# SCH_ESP32-v3_01-12-2025_2025-12-03.net
KiCad netlist of a schematic drawn in EasyEDA
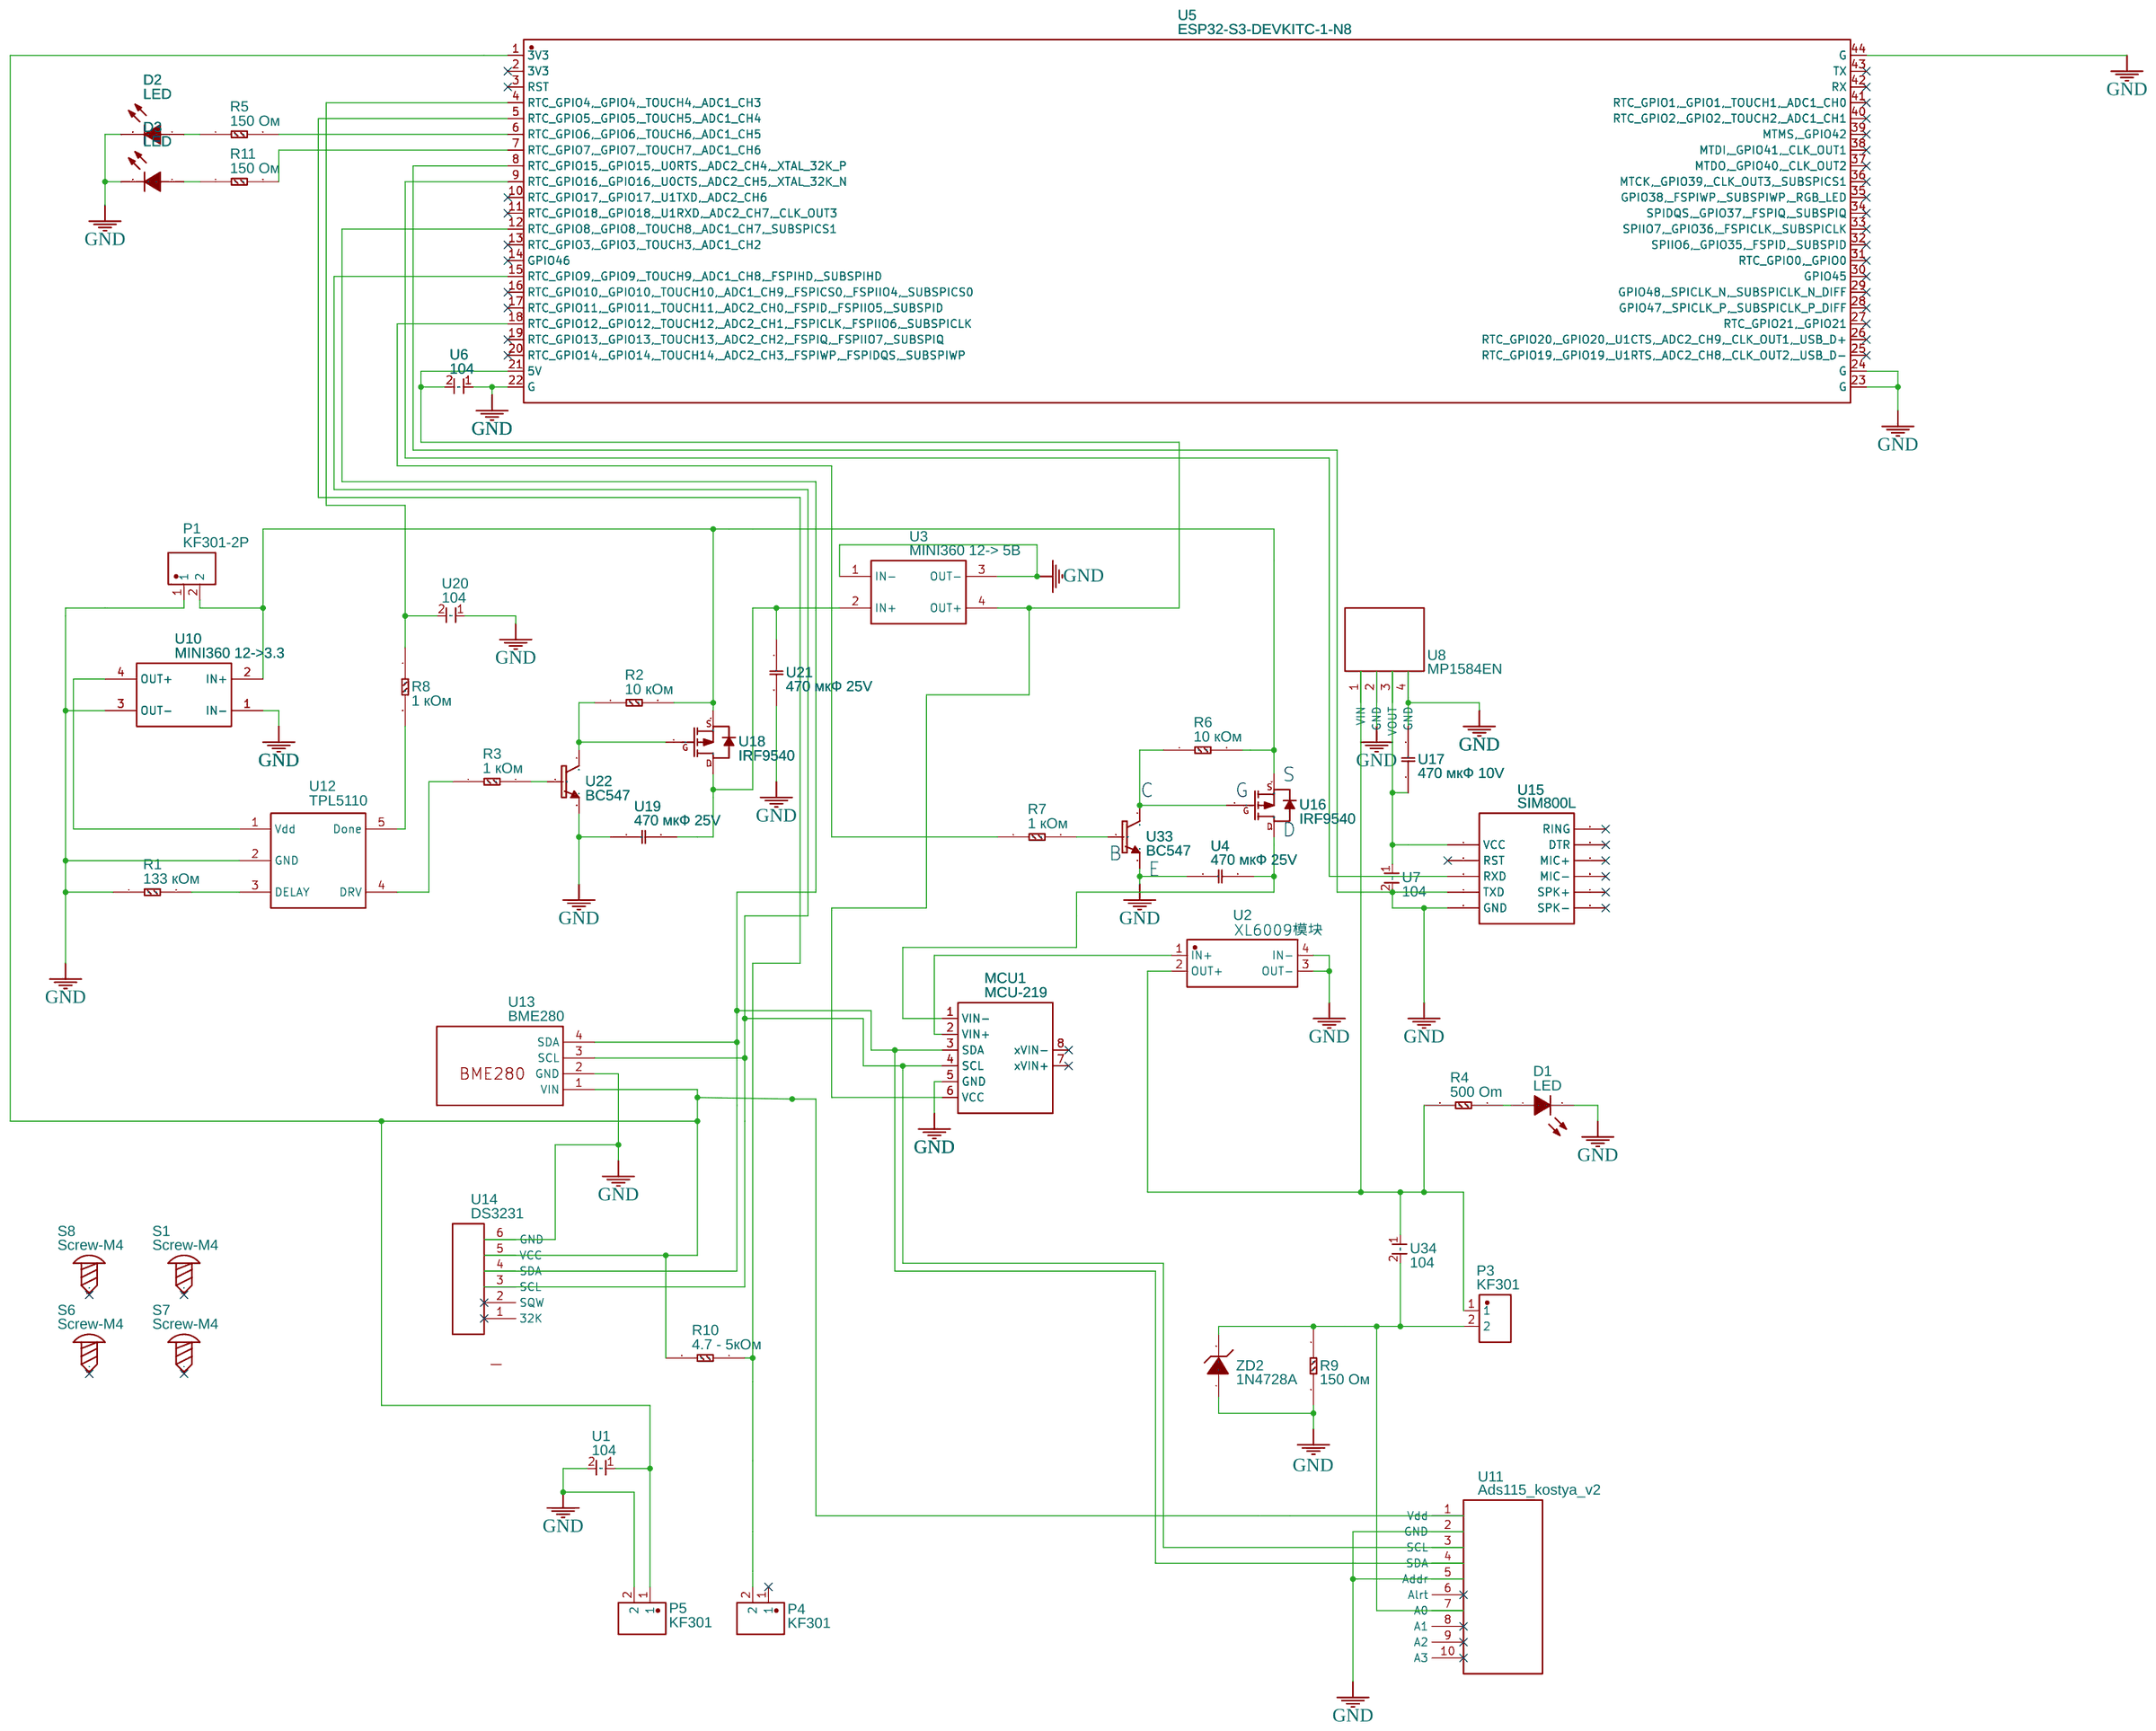
[diagram p0: schematic sheet]

(export (version "E")
  (design (tool "Eeschema 10.0.6"))
  (components
    (comp (ref "D1")
      (value "LED")
      (fields (field (name "Manufacturer Part") "5600") (field (name "Manufacturer") "VccLite"))
      (libsource (lib "") (part "LED_1"))
    )
    (comp (ref "D2")
      (value "LED")
      (fields (field (name "Manufacturer Part") "5600") (field (name "Manufacturer") "VccLite"))
      (libsource (lib "") (part "LED"))
    )
    (comp (ref "D3")
      (value "LED")
      (fields (field (name "Manufacturer Part") "5600") (field (name "Manufacturer") "VccLite"))
      (libsource (lib "") (part "LED"))
    )
    (comp (ref "MCU1") (value "MCU-219") (libsource (lib "") (part "MCU-219")))
    (comp (ref "P1")
      (value "KF301-2P")
      (fields (field (name "Manufacturer Part") "KF301-2P接线端子"))
      (libsource (lib "") (part "KF301-2P VCC Y GND"))
    )
    (comp (ref "P3")
      (value "KF301")
      (fields (field (name "Manufacturer Part") "KF301-2P接线端子"))
      (libsource (lib "") (part "KF301-2P VCC Y GND_2"))
    )
    (comp (ref "P4")
      (value "KF301")
      (fields (field (name "Manufacturer Part") "KF301-2P接线端子"))
      (libsource (lib "") (part "KF301-2P VCC Y GND_1"))
    )
    (comp (ref "P5")
      (value "KF301")
      (fields (field (name "Manufacturer Part") "KF301-2P接线端子"))
      (libsource (lib "") (part "KF301-2P VCC Y GND_1"))
    )
    (comp (ref "R1") (value "133 кОм") (libsource (lib "") (part "R_")))
    (comp (ref "R2") (value "10 кОм") (libsource (lib "") (part "R_")))
    (comp (ref "R3") (value "1 кОм") (libsource (lib "") (part "R_")))
    (comp (ref "R4") (value "500 Om") (libsource (lib "") (part "R__2")))
    (comp (ref "R5") (value "150 Ом") (libsource (lib "") (part "R_")))
    (comp (ref "R6") (value "10 кОм") (libsource (lib "") (part "R_")))
    (comp (ref "R7") (value "1 кОм") (libsource (lib "") (part "R_")))
    (comp (ref "R8") (value "1 кОм") (libsource (lib "") (part "R__1")))
    (comp (ref "R9") (value "150 Ом") (libsource (lib "") (part "R__1")))
    (comp (ref "R10") (value "4.7 - 5кОм") (libsource (lib "") (part "R__2")))
    (comp (ref "R11") (value "150 Ом") (libsource (lib "") (part "R_")))
    (comp (ref "S1") (value "Screw-M4") (libsource (lib "") (part "Screw-M4")))
    (comp (ref "S6") (value "Screw-M4") (libsource (lib "") (part "Screw-M4")))
    (comp (ref "S7") (value "Screw-M4") (libsource (lib "") (part "Screw-M4")))
    (comp (ref "S8") (value "Screw-M4") (libsource (lib "") (part "Screw-M4")))
    (comp (ref "U1")
      (value "104")
      (fields (field (name "Manufacturer") "Fe"))
      (libsource (lib "") (part "104_1"))
    )
    (comp (ref "U2")
      (value "XL6009模块")
      (fields (field (name "Manufacturer Part") "xl6009模块"))
      (libsource (lib "") (part "XL6009模块"))
    )
    (comp (ref "U3")
      (value "MINI360 12-> 5В")
      (fields (field (name "Manufacturer Part") "Mini360"))
      (libsource (lib "") (part "MINI360BUCK_1"))
    )
    (comp (ref "U4") (value "470 мкФ 25V") (libsource (lib "") (part "C__1")))
    (comp (ref "U5")
      (value "ESP32-S3-DEVKITC-1-N8")
      (fields (field (name "Manufacturer") "ESPRESSIF(乐鑫)"))
      (libsource (lib "") (part "ESP32-S3-DEVKITC-1-N8"))
    )
    (comp (ref "U6")
      (value "104")
      (fields (field (name "Manufacturer") "Fe"))
      (libsource (lib "") (part "104_1"))
    )
    (comp (ref "U7")
      (value "104")
      (fields (field (name "Manufacturer") "Fe"))
      (libsource (lib "") (part "104"))
    )
    (comp (ref "U8") (value "MP1584EN") (libsource (lib "") (part "MP1584EN")))
    (comp (ref "U10")
      (value "MINI360 12->3.3")
      (fields (field (name "Manufacturer Part") "Mini360"))
      (libsource (lib "") (part "MINI360BUCK"))
    )
    (comp (ref "U11") (value "Ads115_kostya_v2") (libsource (lib "") (part "Ads115_kostya_v2")))
    (comp (ref "U12")
      (value "TPL5110")
      (fields (field (name "Manufacturer Part") "3435"))
      (libsource (lib "") (part "ADAFRUIT TPL5110 BREAKOUT"))
    )
    (comp (ref "U13") (value "BME280") (libsource (lib "") (part "BME280")))
    (comp (ref "U14") (value "DS3231") (libsource (lib "") (part "DS3231 upright")))
    (comp (ref "U15") (value "SIM800L") (libsource (lib "") (part "SIM800L")))
    (comp (ref "U16") (value "IRF9540") (libsource (lib "") (part "IRF9540")))
    (comp (ref "U17") (value "470 мкФ 10V") (libsource (lib "") (part "C_")))
    (comp (ref "U18") (value "IRF9540") (libsource (lib "") (part "IRF9540")))
    (comp (ref "U19") (value "470 мкФ 25V") (libsource (lib "") (part "C__1")))
    (comp (ref "U20")
      (value "104")
      (fields (field (name "Manufacturer") "Fe"))
      (libsource (lib "") (part "104_1"))
    )
    (comp (ref "U21") (value "470 мкФ 25V") (libsource (lib "") (part "C_")))
    (comp (ref "U22") (value "BC547") (libsource (lib "") (part "BC547")))
    (comp (ref "U33") (value "BC547") (libsource (lib "") (part "BC547")))
    (comp (ref "U34")
      (value "104")
      (fields (field (name "Manufacturer") "Fe"))
      (libsource (lib "") (part "104"))
    )
    (comp (ref "ZD2")
      (value "1N4728A")
      (fields (field (name "Manufacturer") "ST(先科)"))
      (libsource (lib "") (part "1N4728A"))
    )
  )
  (nets
    (net (code "1") (name "GND") (class "Default")
      (node (ref "D1") (pin "2") (pinfunction "K_2") (pintype "unspecified"))
      (node (ref "D2") (pin "2") (pinfunction "K_2") (pintype "unspecified"))
      (node (ref "D3") (pin "2") (pinfunction "K_2") (pintype "unspecified"))
      (node (ref "MCU1") (pin "5") (pinfunction "GND_5") (pintype "unspecified"))
      (node (ref "P1") (pin "1") (pinfunction "1_1") (pintype "unspecified"))
      (node (ref "P5") (pin "2") (pinfunction "2_2") (pintype "unspecified"))
      (node (ref "R1") (pin "1") (pinfunction "1_1") (pintype "unspecified"))
      (node (ref "R9") (pin "2") (pinfunction "2_2") (pintype "unspecified"))
      (node (ref "U1") (pin "2") (pinfunction "2_2") (pintype "unspecified"))
      (node (ref "U10") (pin "1") (pinfunction "IN-_1") (pintype "unspecified"))
      (node (ref "U10") (pin "3") (pinfunction "OUT-_3") (pintype "unspecified"))
      (node (ref "U11") (pin "2") (pinfunction "GND_2") (pintype "unspecified"))
      (node (ref "U11") (pin "5") (pinfunction "Addr_5") (pintype "unspecified"))
      (node (ref "U12") (pin "2") (pinfunction "GND_2") (pintype "unspecified"))
      (node (ref "U13") (pin "2") (pinfunction "GND_2") (pintype "unspecified"))
      (node (ref "U14") (pin "6") (pinfunction "GND_6") (pintype "unspecified"))
      (node (ref "U15") (pin "4") (pinfunction "TXD_4") (pintype "unspecified"))
      (node (ref "U15") (pin "5") (pinfunction "GND_5") (pintype "unspecified"))
      (node (ref "U17") (pin "1") (pinfunction "1_1") (pintype "unspecified"))
      (node (ref "U19") (pin "1") (pinfunction "1_1") (pintype "unspecified"))
      (node (ref "U2") (pin "3") (pinfunction "OUT-_3") (pintype "unspecified"))
      (node (ref "U2") (pin "4") (pinfunction "IN-_4") (pintype "unspecified"))
      (node (ref "U20") (pin "1") (pinfunction "1_1") (pintype "unspecified"))
      (node (ref "U21") (pin "2") (pinfunction "2_2") (pintype "unspecified"))
      (node (ref "U22") (pin "3") (pinfunction "E_3") (pintype "unspecified"))
      (node (ref "U3") (pin "1") (pinfunction "IN-_1") (pintype "unspecified"))
      (node (ref "U3") (pin "3") (pinfunction "OUT-_3") (pintype "unspecified"))
      (node (ref "U33") (pin "3") (pinfunction "E_3") (pintype "unspecified"))
      (node (ref "U4") (pin "1") (pinfunction "1_1") (pintype "unspecified"))
      (node (ref "U5") (pin "22") (pinfunction "G_22") (pintype "unspecified"))
      (node (ref "U5") (pin "23") (pinfunction "G_23") (pintype "unspecified"))
      (node (ref "U5") (pin "24") (pinfunction "G_24") (pintype "unspecified"))
      (node (ref "U5") (pin "44") (pinfunction "G_44") (pintype "unspecified"))
      (node (ref "U5") (pin "8") (pinfunction "RTC_GPIO15,_GPIO15,_U0RTS,_ADC2_CH4,_XTAL_32K_P_8") (pintype "unspecified"))
      (node (ref "U6") (pin "1") (pinfunction "1_1") (pintype "unspecified"))
      (node (ref "U7") (pin "2") (pinfunction "2_2") (pintype "unspecified"))
      (node (ref "U8") (pin "2") (pinfunction "GND_2") (pintype "unspecified"))
      (node (ref "U8") (pin "4") (pinfunction "GND_4") (pintype "unspecified"))
      (node (ref "ZD2") (pin "1") (pinfunction "A_1") (pintype "unspecified"))
    )
    (net (code "2") (name "Net-(D1-A)") (class "Default")
      (node (ref "D1") (pin "1") (pinfunction "A_1") (pintype "unspecified"))
      (node (ref "R4") (pin "1") (pinfunction "1_1") (pintype "unspecified"))
    )
    (net (code "3") (name "Net-(D2-A)") (class "Default")
      (node (ref "D2") (pin "1") (pinfunction "A_1") (pintype "unspecified"))
      (node (ref "R5") (pin "1") (pinfunction "1_1") (pintype "unspecified"))
    )
    (net (code "4") (name "Net-(D3-A)") (class "Default")
      (node (ref "D3") (pin "1") (pinfunction "A_1") (pintype "unspecified"))
      (node (ref "R11") (pin "1") (pinfunction "1_1") (pintype "unspecified"))
    )
    (net (code "5") (name "Net-(MCU1-SCL)") (class "Default")
      (node (ref "MCU1") (pin "4") (pinfunction "SCL_4") (pintype "unspecified"))
      (node (ref "U11") (pin "3") (pinfunction "SCL_3") (pintype "unspecified"))
      (node (ref "U13") (pin "3") (pinfunction "SCL_3") (pintype "unspecified"))
      (node (ref "U14") (pin "3") (pinfunction "SCL_3") (pintype "unspecified"))
      (node (ref "U5") (pin "15") (pinfunction "RTC_GPIO9,_GPIO9,_TOUCH9,_ADC1_CH8,_FSPIHD,_SUBSPIHD_15") (pintype "unspecified"))
    )
    (net (code "6") (name "Net-(MCU1-SDA)") (class "Default")
      (node (ref "MCU1") (pin "3") (pinfunction "SDA_3") (pintype "unspecified"))
      (node (ref "U11") (pin "4") (pinfunction "SDA_4") (pintype "unspecified"))
      (node (ref "U13") (pin "4") (pinfunction "SDA_4") (pintype "unspecified"))
      (node (ref "U14") (pin "4") (pinfunction "SDA_4") (pintype "unspecified"))
      (node (ref "U5") (pin "12") (pinfunction "RTC_GPIO8,_GPIO8,_TOUCH8,_ADC1_CH7,_SUBSPICS1_12") (pintype "unspecified"))
    )
    (net (code "7") (name "Net-(MCU1-VCC)") (class "Default")
      (node (ref "MCU1") (pin "6") (pinfunction "VCC_6") (pintype "unspecified"))
      (node (ref "U3") (pin "4") (pinfunction "OUT+_4") (pintype "unspecified"))
      (node (ref "U5") (pin "21") (pinfunction "5V_21") (pintype "unspecified"))
      (node (ref "U6") (pin "2") (pinfunction "2_2") (pintype "unspecified"))
    )
    (net (code "8") (name "Net-(MCU1-VIN+)") (class "Default")
      (node (ref "MCU1") (pin "2") (pinfunction "VIN+_2") (pintype "unspecified"))
      (node (ref "U2") (pin "1") (pinfunction "IN+_1") (pintype "unspecified"))
    )
    (net (code "9") (name "Net-(MCU1-VIN-)") (class "Default")
      (node (ref "MCU1") (pin "1") (pinfunction "VIN-_1") (pintype "unspecified"))
      (node (ref "U16") (pin "2") (pinfunction "D_2") (pintype "unspecified"))
      (node (ref "U4") (pin "2") (pinfunction "2_2") (pintype "unspecified"))
    )
    (net (code "10") (name "Net-(U2-OUT+)") (class "Default")
      (node (ref "P3") (pin "1") (pinfunction "1_1") (pintype "unspecified"))
      (node (ref "R4") (pin "2") (pinfunction "2_2") (pintype "unspecified"))
      (node (ref "U2") (pin "2") (pinfunction "OUT+_2") (pintype "unspecified"))
      (node (ref "U34") (pin "1") (pinfunction "1_1") (pintype "unspecified"))
      (node (ref "U8") (pin "1") (pinfunction "VIN_1") (pintype "unspecified"))
    )
    (net (code "11") (name "Net-(U5-RTC_GPIO4,_GPIO4,_TOUCH4,_ADC1_CH3)") (class "Default")
      (node (ref "R8") (pin "1") (pinfunction "1_1") (pintype "unspecified"))
      (node (ref "U20") (pin "2") (pinfunction "2_2") (pintype "unspecified"))
      (node (ref "U5") (pin "4") (pinfunction "RTC_GPIO4,_GPIO4,_TOUCH4,_ADC1_CH3_4") (pintype "unspecified"))
    )
    (net (code "12") (name "Net-(U5-RTC_GPIO5,_GPIO5,_TOUCH5,_ADC1_CH4)") (class "Default")
      (node (ref "P4") (pin "2") (pinfunction "2_2") (pintype "unspecified"))
      (node (ref "R10") (pin "1") (pinfunction "1_1") (pintype "unspecified"))
      (node (ref "U5") (pin "5") (pinfunction "RTC_GPIO5,_GPIO5,_TOUCH5,_ADC1_CH4_5") (pintype "unspecified"))
    )
    (net (code "13") (name "Net-(U5-RTC_GPIO6,_GPIO6,_TOUCH6,_ADC1_CH5)") (class "Default")
      (node (ref "R5") (pin "2") (pinfunction "2_2") (pintype "unspecified"))
      (node (ref "U5") (pin "6") (pinfunction "RTC_GPIO6,_GPIO6,_TOUCH6,_ADC1_CH5_6") (pintype "unspecified"))
    )
    (net (code "14") (name "Net-(U5-RTC_GPIO7,_GPIO7,_TOUCH7,_ADC1_CH6)") (class "Default")
      (node (ref "R11") (pin "2") (pinfunction "2_2") (pintype "unspecified"))
      (node (ref "U5") (pin "7") (pinfunction "RTC_GPIO7,_GPIO7,_TOUCH7,_ADC1_CH6_7") (pintype "unspecified"))
    )
    (net (code "15") (name "Net-(U5-RTC_GPIO12,_GPIO12,_TOUCH12,_ADC2_CH1,_FSPICLK,_FSPIIO6,_SUBSPICLK)") (class "Default")
      (node (ref "R7") (pin "1") (pinfunction "1_1") (pintype "unspecified"))
      (node (ref "U5") (pin "18") (pinfunction "RTC_GPIO12,_GPIO12,_TOUCH12,_ADC2_CH1,_FSPICLK,_FSPIIO6,_SUBSPICLK_18") (pintype "unspecified"))
    )
    (net (code "16") (name "Net-(U10-IN+)") (class "Default")
      (node (ref "P1") (pin "2") (pinfunction "2_2") (pintype "unspecified"))
      (node (ref "R2") (pin "2") (pinfunction "2_2") (pintype "unspecified"))
      (node (ref "R6") (pin "2") (pinfunction "2_2") (pintype "unspecified"))
      (node (ref "U10") (pin "2") (pinfunction "IN+_2") (pintype "unspecified"))
      (node (ref "U16") (pin "3") (pinfunction "S_3") (pintype "unspecified"))
      (node (ref "U18") (pin "3") (pinfunction "S_3") (pintype "unspecified"))
    )
    (net (code "17") (name "Net-(U10-OUT+)") (class "Default")
      (node (ref "U10") (pin "4") (pinfunction "OUT+_4") (pintype "unspecified"))
      (node (ref "U12") (pin "1") (pinfunction "Vdd_1") (pintype "unspecified"))
    )
    (net (code "18") (name "Net-(U11-A0)") (class "Default")
      (node (ref "P3") (pin "2") (pinfunction "2_2") (pintype "unspecified"))
      (node (ref "R9") (pin "1") (pinfunction "1_1") (pintype "unspecified"))
      (node (ref "U11") (pin "7") (pinfunction "A0_7") (pintype "unspecified"))
      (node (ref "U34") (pin "2") (pinfunction "2_2") (pintype "unspecified"))
      (node (ref "ZD2") (pin "2") (pinfunction "K_2") (pintype "unspecified"))
    )
    (net (code "19") (name "Net-(U11-Vdd)") (class "Default")
      (node (ref "P5") (pin "1") (pinfunction "1_1") (pintype "unspecified"))
      (node (ref "R10") (pin "2") (pinfunction "2_2") (pintype "unspecified"))
      (node (ref "U1") (pin "1") (pinfunction "1_1") (pintype "unspecified"))
      (node (ref "U11") (pin "1") (pinfunction "Vdd_1") (pintype "unspecified"))
      (node (ref "U13") (pin "1") (pinfunction "VIN_1") (pintype "unspecified"))
      (node (ref "U14") (pin "5") (pinfunction "VCC_5") (pintype "unspecified"))
      (node (ref "U5") (pin "1") (pinfunction "3V3_1") (pintype "unspecified"))
    )
    (net (code "20") (name "Net-(U12-DELAY)") (class "Default")
      (node (ref "R1") (pin "2") (pinfunction "2_2") (pintype "unspecified"))
      (node (ref "U12") (pin "3") (pinfunction "DELAY_3") (pintype "unspecified"))
    )
    (net (code "21") (name "Net-(U12-DRV)") (class "Default")
      (node (ref "R3") (pin "1") (pinfunction "1_1") (pintype "unspecified"))
      (node (ref "U12") (pin "4") (pinfunction "DRV_4") (pintype "unspecified"))
    )
    (net (code "22") (name "Net-(U12-Done)") (class "Default")
      (node (ref "R8") (pin "2") (pinfunction "2_2") (pintype "unspecified"))
      (node (ref "U12") (pin "5") (pinfunction "Done_5") (pintype "unspecified"))
    )
    (net (code "23") (name "Net-(U15-RXD)") (class "Default")
      (node (ref "U15") (pin "3") (pinfunction "RXD_3") (pintype "unspecified"))
      (node (ref "U5") (pin "9") (pinfunction "RTC_GPIO16,_GPIO16,_U0CTS,_ADC2_CH5,_XTAL_32K_N_9") (pintype "unspecified"))
    )
    (net (code "24") (name "Net-(U15-VCC)") (class "Default")
      (node (ref "U15") (pin "1") (pinfunction "VCC_1") (pintype "unspecified"))
      (node (ref "U17") (pin "2") (pinfunction "2_2") (pintype "unspecified"))
      (node (ref "U7") (pin "1") (pinfunction "1_1") (pintype "unspecified"))
      (node (ref "U8") (pin "3") (pinfunction "VOUT_3") (pintype "unspecified"))
    )
    (net (code "25") (name "Net-(U16-G)") (class "Default")
      (node (ref "R6") (pin "1") (pinfunction "1_1") (pintype "unspecified"))
      (node (ref "U16") (pin "1") (pinfunction "G_1") (pintype "unspecified"))
      (node (ref "U33") (pin "1") (pinfunction "C_1") (pintype "unspecified"))
    )
    (net (code "26") (name "Net-(U18-D)") (class "Default")
      (node (ref "U18") (pin "2") (pinfunction "D_2") (pintype "unspecified"))
      (node (ref "U19") (pin "2") (pinfunction "2_2") (pintype "unspecified"))
      (node (ref "U21") (pin "1") (pinfunction "1_1") (pintype "unspecified"))
      (node (ref "U3") (pin "2") (pinfunction "IN+_2") (pintype "unspecified"))
    )
    (net (code "27") (name "Net-(U18-G)") (class "Default")
      (node (ref "R2") (pin "1") (pinfunction "1_1") (pintype "unspecified"))
      (node (ref "U18") (pin "1") (pinfunction "G_1") (pintype "unspecified"))
      (node (ref "U22") (pin "1") (pinfunction "C_1") (pintype "unspecified"))
    )
    (net (code "28") (name "Net-(U22-B)") (class "Default")
      (node (ref "R3") (pin "2") (pinfunction "2_2") (pintype "unspecified"))
      (node (ref "U22") (pin "2") (pinfunction "B_2") (pintype "unspecified"))
    )
    (net (code "29") (name "Net-(U33-B)") (class "Default")
      (node (ref "R7") (pin "2") (pinfunction "2_2") (pintype "unspecified"))
      (node (ref "U33") (pin "2") (pinfunction "B_2") (pintype "unspecified"))
    )
    (net (code "30") (name "unconnected-(MCU1-xVIN+-Pad7)") (class "Default")
      (node (ref "MCU1") (pin "7") (pinfunction "xVIN+_7") (pintype "unspecified+no_connect"))
    )
    (net (code "31") (name "unconnected-(MCU1-xVIN--Pad8)") (class "Default")
      (node (ref "MCU1") (pin "8") (pinfunction "xVIN-_8") (pintype "unspecified+no_connect"))
    )
    (net (code "32") (name "unconnected-(P4-Pad1)") (class "Default")
      (node (ref "P4") (pin "1") (pinfunction "1_1") (pintype "unspecified+no_connect"))
    )
    (net (code "33") (name "unconnected-(S1-Pad1)") (class "Default")
      (node (ref "S1") (pin "1") (pinfunction "1_1") (pintype "unspecified+no_connect"))
    )
    (net (code "34") (name "unconnected-(S6-Pad1)") (class "Default")
      (node (ref "S6") (pin "1") (pinfunction "1_1") (pintype "unspecified+no_connect"))
    )
    (net (code "35") (name "unconnected-(S7-Pad1)") (class "Default")
      (node (ref "S7") (pin "1") (pinfunction "1_1") (pintype "unspecified+no_connect"))
    )
    (net (code "36") (name "unconnected-(S8-Pad1)") (class "Default")
      (node (ref "S8") (pin "1") (pinfunction "1_1") (pintype "unspecified+no_connect"))
    )
    (net (code "37") (name "unconnected-(U5-3V3-Pad2)") (class "Default")
      (node (ref "U5") (pin "2") (pinfunction "3V3_2") (pintype "unspecified+no_connect"))
    )
    (net (code "38") (name "unconnected-(U5-GPIO38,_FSPIWP,_SUBSPIWP,_RGB_LED-Pad35)") (class "Default")
      (node (ref "U5") (pin "35") (pinfunction "GPIO38,_FSPIWP,_SUBSPIWP,_RGB_LED_35") (pintype "unspecified+no_connect"))
    )
    (net (code "39") (name "unconnected-(U5-GPIO45-Pad30)") (class "Default")
      (node (ref "U5") (pin "30") (pinfunction "GPIO45_30") (pintype "unspecified+no_connect"))
    )
    (net (code "40") (name "unconnected-(U5-GPIO46-Pad14)") (class "Default")
      (node (ref "U5") (pin "14") (pinfunction "GPIO46_14") (pintype "unspecified+no_connect"))
    )
    (net (code "41") (name "unconnected-(U5-GPIO47,_SPICLK_P,_SUBSPICLK_P_DIFF-Pad28)") (class "Default")
      (node (ref "U5") (pin "28") (pinfunction "GPIO47,_SPICLK_P,_SUBSPICLK_P_DIFF_28") (pintype "unspecified+no_connect"))
    )
    (net (code "42") (name "unconnected-(U5-GPIO48,_SPICLK_N,_SUBSPICLK_N_DIFF-Pad29)") (class "Default")
      (node (ref "U5") (pin "29") (pinfunction "GPIO48,_SPICLK_N,_SUBSPICLK_N_DIFF_29") (pintype "unspecified+no_connect"))
    )
    (net (code "43") (name "unconnected-(U5-MTCK,_GPIO39,_CLK_OUT3,_SUBSPICS1-Pad36)") (class "Default")
      (node (ref "U5") (pin "36") (pinfunction "MTCK,_GPIO39,_CLK_OUT3,_SUBSPICS1_36") (pintype "unspecified+no_connect"))
    )
    (net (code "44") (name "unconnected-(U5-MTDI,_GPIO41,_CLK_OUT1-Pad38)") (class "Default")
      (node (ref "U5") (pin "38") (pinfunction "MTDI,_GPIO41,_CLK_OUT1_38") (pintype "unspecified+no_connect"))
    )
    (net (code "45") (name "unconnected-(U5-MTDO,_GPIO40,_CLK_OUT2-Pad37)") (class "Default")
      (node (ref "U5") (pin "37") (pinfunction "MTDO,_GPIO40,_CLK_OUT2_37") (pintype "unspecified+no_connect"))
    )
    (net (code "46") (name "unconnected-(U5-MTMS,_GPIO42-Pad39)") (class "Default")
      (node (ref "U5") (pin "39") (pinfunction "MTMS,_GPIO42_39") (pintype "unspecified+no_connect"))
    )
    (net (code "47") (name "unconnected-(U5-RST-Pad3)") (class "Default")
      (node (ref "U5") (pin "3") (pinfunction "RST_3") (pintype "unspecified+no_connect"))
    )
    (net (code "48") (name "unconnected-(U5-RTC_GPIO0,_GPIO0-Pad31)") (class "Default")
      (node (ref "U5") (pin "31") (pinfunction "RTC_GPIO0,_GPIO0_31") (pintype "unspecified+no_connect"))
    )
    (net (code "49") (name "unconnected-(U5-RTC_GPIO1,_GPIO1,_TOUCH1,_ADC1_CH0-Pad41)") (class "Default")
      (node (ref "U5") (pin "41") (pinfunction "RTC_GPIO1,_GPIO1,_TOUCH1,_ADC1_CH0_41") (pintype "unspecified+no_connect"))
    )
    (net (code "50") (name "unconnected-(U5-RTC_GPIO2,_GPIO2,_TOUCH2,_ADC1_CH1-Pad40)") (class "Default")
      (node (ref "U5") (pin "40") (pinfunction "RTC_GPIO2,_GPIO2,_TOUCH2,_ADC1_CH1_40") (pintype "unspecified+no_connect"))
    )
    (net (code "51") (name "unconnected-(U5-RTC_GPIO3,_GPIO3,_TOUCH3,_ADC1_CH2-Pad13)") (class "Default")
      (node (ref "U5") (pin "13") (pinfunction "RTC_GPIO3,_GPIO3,_TOUCH3,_ADC1_CH2_13") (pintype "unspecified+no_connect"))
    )
    (net (code "52") (name "unconnected-(U5-RTC_GPIO10,_GPIO10,_TOUCH10,_ADC1_CH9,_FSPICS0,_FSPIIO4,_SUBSPICS0-Pad16)") (class "Default")
      (node (ref "U5") (pin "16") (pinfunction "RTC_GPIO10,_GPIO10,_TOUCH10,_ADC1_CH9,_FSPICS0,_FSPIIO4,_SUBSPICS0_16") (pintype "unspecified+no_connect"))
    )
    (net (code "53") (name "unconnected-(U5-RTC_GPIO11,_GPIO11,_TOUCH11,_ADC2_CH0,_FSPID,_FSPIIO5,_SUBSPID-Pad17)") (class "Default")
      (node (ref "U5") (pin "17") (pinfunction "RTC_GPIO11,_GPIO11,_TOUCH11,_ADC2_CH0,_FSPID,_FSPIIO5,_SUBSPID_17") (pintype "unspecified+no_connect"))
    )
    (net (code "54") (name "unconnected-(U5-RTC_GPIO13,_GPIO13,_TOUCH13,_ADC2_CH2,_FSPIQ,_FSPIIO7,_SUBSPIQ-Pad19)") (class "Default")
      (node (ref "U5") (pin "19") (pinfunction "RTC_GPIO13,_GPIO13,_TOUCH13,_ADC2_CH2,_FSPIQ,_FSPIIO7,_SUBSPIQ_19") (pintype "unspecified+no_connect"))
    )
    (net (code "55") (name "unconnected-(U5-RTC_GPIO14,_GPIO14,_TOUCH14,_ADC2_CH3,_FSPIWP,_FSPIDQS,_SUBSPIWP-Pad20)") (class "Default")
      (node (ref "U5") (pin "20") (pinfunction "RTC_GPIO14,_GPIO14,_TOUCH14,_ADC2_CH3,_FSPIWP,_FSPIDQS,_SUBSPIWP_20") (pintype "unspecified+no_connect"))
    )
    (net (code "56") (name "unconnected-(U5-RTC_GPIO17,_GPIO17,_U1TXD,_ADC2_CH6-Pad10)") (class "Default")
      (node (ref "U5") (pin "10") (pinfunction "RTC_GPIO17,_GPIO17,_U1TXD,_ADC2_CH6_10") (pintype "unspecified+no_connect"))
    )
    (net (code "57") (name "unconnected-(U5-RTC_GPIO18,_GPIO18,_U1RXD,_ADC2_CH7,_CLK_OUT3-Pad11)") (class "Default")
      (node (ref "U5") (pin "11") (pinfunction "RTC_GPIO18,_GPIO18,_U1RXD,_ADC2_CH7,_CLK_OUT3_11") (pintype "unspecified+no_connect"))
    )
    (net (code "58") (name "unconnected-(U5-RTC_GPIO19,_GPIO19,_U1RTS,_ADC2_CH8,_CLK_OUT2,_USB_D--Pad25)") (class "Default")
      (node (ref "U5") (pin "25") (pinfunction "RTC_GPIO19,_GPIO19,_U1RTS,_ADC2_CH8,_CLK_OUT2,_USB_D-_25") (pintype "unspecified+no_connect"))
    )
    (net (code "59") (name "unconnected-(U5-RTC_GPIO20,_GPIO20,_U1CTS,_ADC2_CH9,_CLK_OUT1,_USB_D+-Pad26)") (class "Default")
      (node (ref "U5") (pin "26") (pinfunction "RTC_GPIO20,_GPIO20,_U1CTS,_ADC2_CH9,_CLK_OUT1,_USB_D+_26") (pintype "unspecified+no_connect"))
    )
    (net (code "60") (name "unconnected-(U5-RTC_GPIO21,_GPIO21-Pad27)") (class "Default")
      (node (ref "U5") (pin "27") (pinfunction "RTC_GPIO21,_GPIO21_27") (pintype "unspecified+no_connect"))
    )
    (net (code "61") (name "unconnected-(U5-RX-Pad42)") (class "Default")
      (node (ref "U5") (pin "42") (pinfunction "RX_42") (pintype "unspecified+no_connect"))
    )
    (net (code "62") (name "unconnected-(U5-SPIDQS,_GPIO37,_FSPIQ,_SUBSPIQ-Pad34)") (class "Default")
      (node (ref "U5") (pin "34") (pinfunction "SPIDQS,_GPIO37,_FSPIQ,_SUBSPIQ_34") (pintype "unspecified+no_connect"))
    )
    (net (code "63") (name "unconnected-(U5-SPIIO6,_GPIO35,_FSPID,_SUBSPID-Pad32)") (class "Default")
      (node (ref "U5") (pin "32") (pinfunction "SPIIO6,_GPIO35,_FSPID,_SUBSPID_32") (pintype "unspecified+no_connect"))
    )
    (net (code "64") (name "unconnected-(U5-SPIIO7,_GPIO36,_FSPICLK,_SUBSPICLK-Pad33)") (class "Default")
      (node (ref "U5") (pin "33") (pinfunction "SPIIO7,_GPIO36,_FSPICLK,_SUBSPICLK_33") (pintype "unspecified+no_connect"))
    )
    (net (code "65") (name "unconnected-(U5-TX-Pad43)") (class "Default")
      (node (ref "U5") (pin "43") (pinfunction "TX_43") (pintype "unspecified+no_connect"))
    )
    (net (code "66") (name "unconnected-(U11-A1-Pad8)") (class "Default")
      (node (ref "U11") (pin "8") (pinfunction "A1_8") (pintype "unspecified+no_connect"))
    )
    (net (code "67") (name "unconnected-(U11-A2-Pad9)") (class "Default")
      (node (ref "U11") (pin "9") (pinfunction "A2_9") (pintype "unspecified+no_connect"))
    )
    (net (code "68") (name "unconnected-(U11-A3-Pad10)") (class "Default")
      (node (ref "U11") (pin "10") (pinfunction "A3_10") (pintype "unspecified+no_connect"))
    )
    (net (code "69") (name "unconnected-(U11-Alrt-Pad6)") (class "Default")
      (node (ref "U11") (pin "6") (pinfunction "Alrt_6") (pintype "unspecified+no_connect"))
    )
    (net (code "70") (name "unconnected-(U14-32K-Pad1)") (class "Default")
      (node (ref "U14") (pin "1") (pinfunction "32K_1") (pintype "unspecified+no_connect"))
    )
    (net (code "71") (name "unconnected-(U14-SQW-Pad2)") (class "Default")
      (node (ref "U14") (pin "2") (pinfunction "SQW_2") (pintype "unspecified+no_connect"))
    )
    (net (code "72") (name "unconnected-(U15-DTR-Pad10)") (class "Default")
      (node (ref "U15") (pin "10") (pinfunction "DTR_10") (pintype "unspecified+no_connect"))
    )
    (net (code "73") (name "unconnected-(U15-MIC+-Pad9)") (class "Default")
      (node (ref "U15") (pin "9") (pinfunction "MIC+_9") (pintype "unspecified+no_connect"))
    )
    (net (code "74") (name "unconnected-(U15-MIC--Pad8)") (class "Default")
      (node (ref "U15") (pin "8") (pinfunction "MIC-_8") (pintype "unspecified+no_connect"))
    )
    (net (code "75") (name "unconnected-(U15-RING-Pad11)") (class "Default")
      (node (ref "U15") (pin "11") (pinfunction "RING_11") (pintype "unspecified+no_connect"))
    )
    (net (code "76") (name "unconnected-(U15-RST-Pad2)") (class "Default")
      (node (ref "U15") (pin "2") (pinfunction "RST_2") (pintype "unspecified+no_connect"))
    )
    (net (code "77") (name "unconnected-(U15-SPK+-Pad7)") (class "Default")
      (node (ref "U15") (pin "7") (pinfunction "SPK+_7") (pintype "unspecified+no_connect"))
    )
    (net (code "78") (name "unconnected-(U15-SPK--Pad6)") (class "Default")
      (node (ref "U15") (pin "6") (pinfunction "SPK-_6") (pintype "unspecified+no_connect"))
    )
  )
)
